# 10_-_LEDS_BUTTONS.net
KiCad netlist of a schematic drawn in Altium Designer
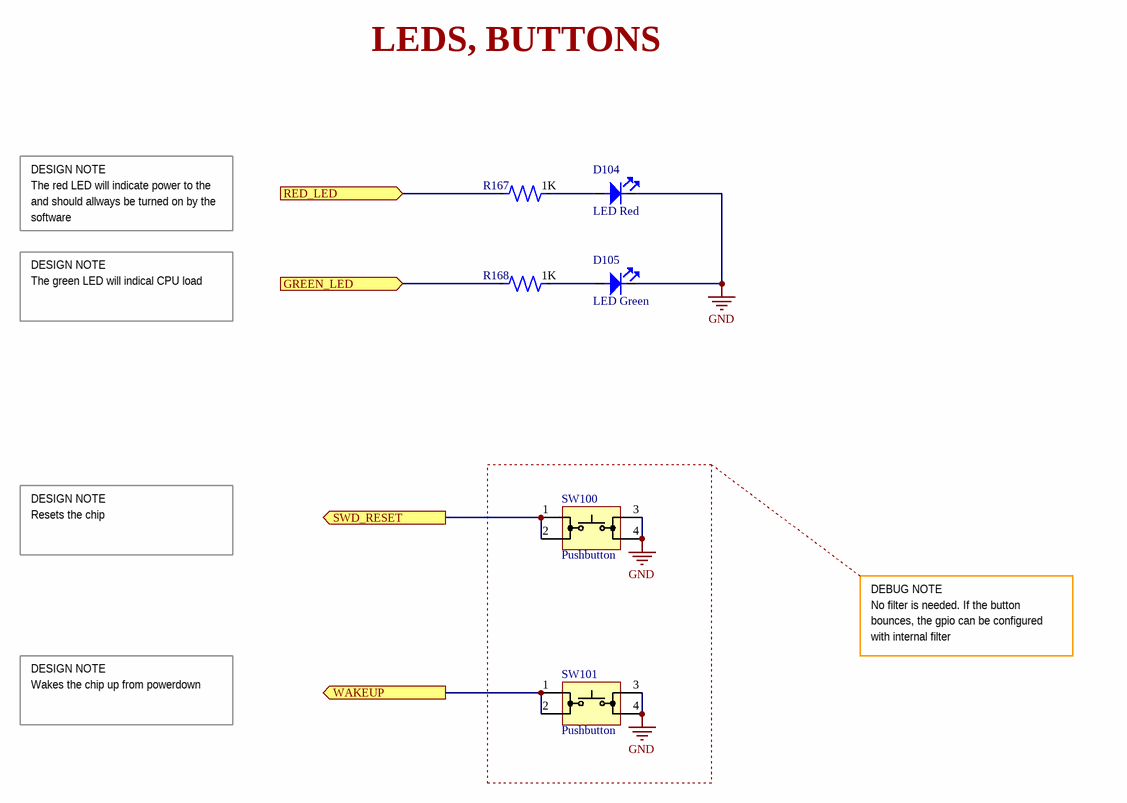
[diagram p0: [10] - LEDS, BUTTONS.SchDoc]

(export (version "E")
  (design (tool "Eeschema 10.0.6"))
  (components
    (comp (ref "D104")
      (value "LED Red")
      (footprint "L0603 RED")
      (description "LED 0603 Red")
      (libsource (lib "Diodes") (part "HSMG-C190"))
    )
    (comp (ref "D105")
      (value "LED Green")
      (footprint "L0603 GREEN")
      (description "LED 0603 Green")
      (libsource (lib "Diodes") (part "HSMG-C196"))
    )
    (comp (ref "R167")
      (value "1K")
      (footprint "R0402")
      (description "R0402")
      (fields (field (name "Comment") "CRCW04020000Z0ED"))
      (libsource (lib "Passive components") (part "CRCW04020000Z0ED"))
    )
    (comp (ref "R168")
      (value "1K")
      (footprint "R0402")
      (description "R0402")
      (fields (field (name "Comment") "CRCW04020000Z0ED"))
      (libsource (lib "Passive components") (part "CRCW04020000Z0ED"))
    )
    (comp (ref "SW100")
      (value "Pushbutton")
      (footprint "KSC222G LFS")
      (description "Pushbutton SMD")
      (libsource (lib "Sensors") (part "KSC222G LFS"))
    )
    (comp (ref "SW101")
      (value "Pushbutton")
      (footprint "KSC222G LFS")
      (description "Pushbutton SMD")
      (libsource (lib "Sensors") (part "KSC222G LFS"))
    )
  )
  (nets
    (net (code "1") (name "/GREEN_LED") (class "Default")
      (node (ref "R168") (pin "1") (pinfunction "1_1") (pintype "passive"))
    )
    (net (code "2") (name "/RED_LED") (class "Default")
      (node (ref "R167") (pin "1") (pinfunction "1_1") (pintype "passive"))
    )
    (net (code "3") (name "/SWD_RESET") (class "Default")
      (node (ref "SW100") (pin "1") (pinfunction "1_1") (pintype "passive"))
      (node (ref "SW100") (pin "2") (pinfunction "2_2") (pintype "passive"))
    )
    (net (code "4") (name "/WAKEUP") (class "Default")
      (node (ref "SW101") (pin "1") (pinfunction "1_1") (pintype "passive"))
      (node (ref "SW101") (pin "2") (pinfunction "2_2") (pintype "passive"))
    )
    (net (code "5") (name "GND") (class "Default")
      (node (ref "D104") (pin "2") (pinfunction "2_2") (pintype "passive"))
      (node (ref "D105") (pin "2") (pinfunction "2_2") (pintype "passive"))
      (node (ref "SW100") (pin "3") (pinfunction "3_3") (pintype "passive"))
      (node (ref "SW100") (pin "4") (pinfunction "4_4") (pintype "passive"))
      (node (ref "SW101") (pin "3") (pinfunction "3_3") (pintype "passive"))
      (node (ref "SW101") (pin "4") (pinfunction "4_4") (pintype "passive"))
    )
    (net (code "6") (name "Net-(R167-3)") (class "Default")
      (node (ref "D104") (pin "1") (pinfunction "1_1") (pintype "passive"))
      (node (ref "R167") (pin "2") (pinfunction "3_2") (pintype "passive"))
    )
    (net (code "7") (name "Net-(R168-3)") (class "Default")
      (node (ref "D105") (pin "1") (pinfunction "1_1") (pintype "passive"))
      (node (ref "R168") (pin "2") (pinfunction "3_2") (pintype "passive"))
    )
  )
)
